# ETH_Wifi.net
KiCad netlist of a schematic drawn in Altium Designer
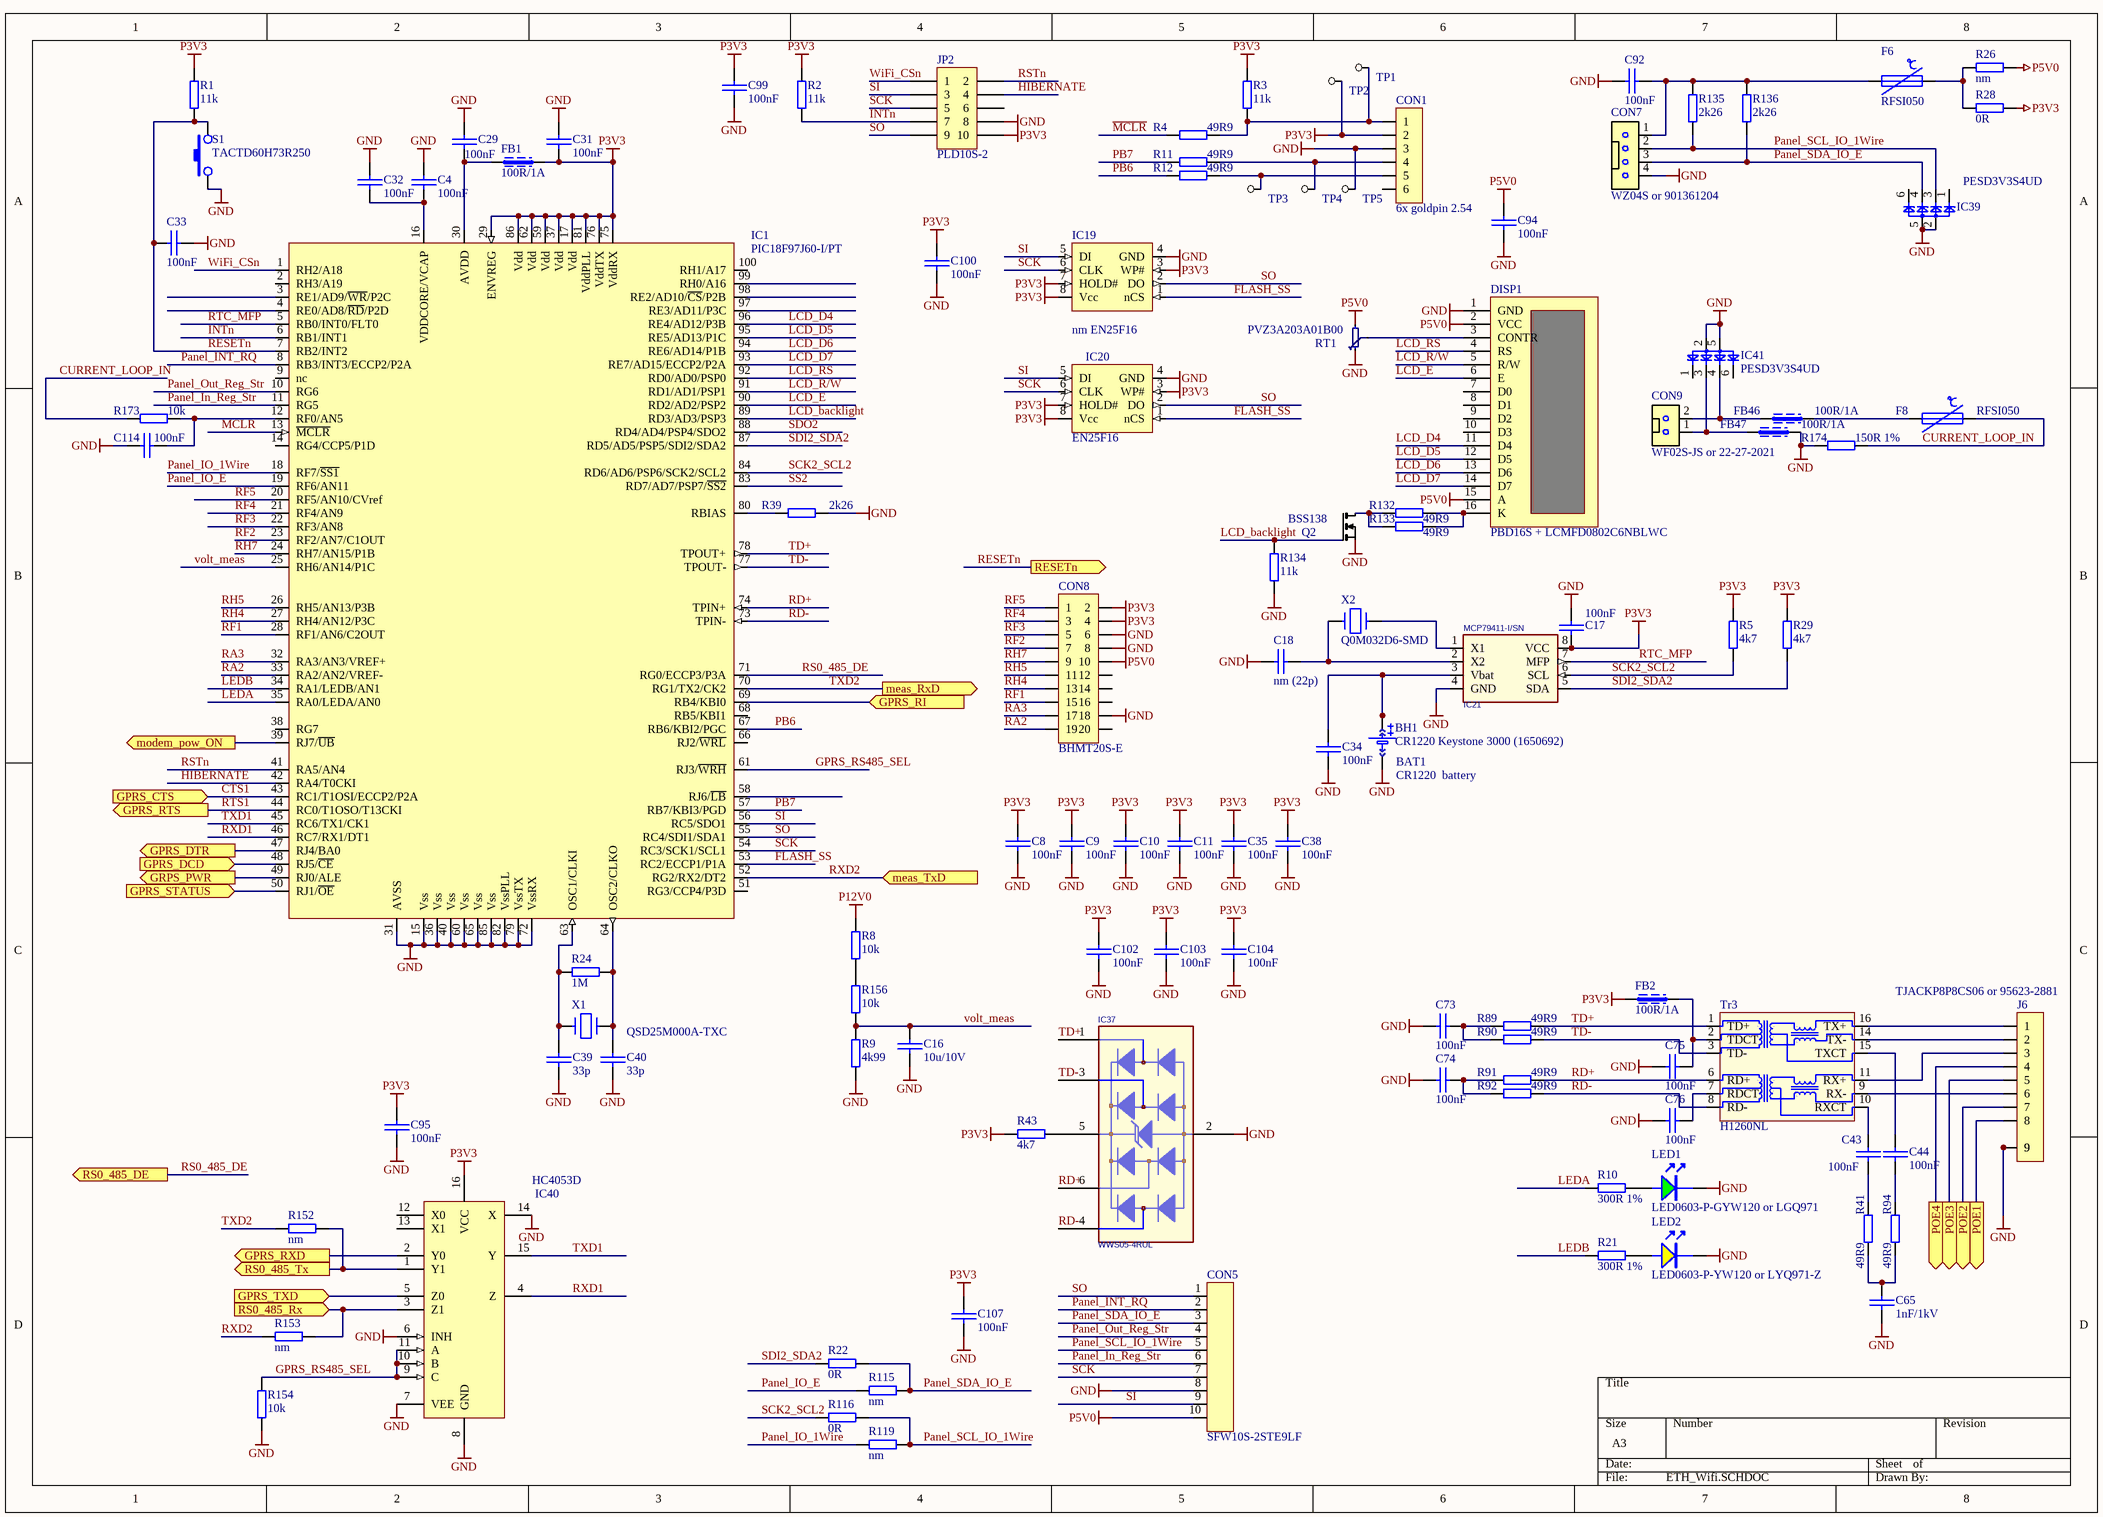
[diagram p0: ETH_Wifi.SCHDOC]

(export (version "E")
  (design (tool "Eeschema 10.0.6"))
  (components
    (comp (ref "BAT1")
      (value "CR1220  battery")
      (footprint "cr1220")
      (description "CR-21220 Battery 3V 35mAh")
      (libsource (lib "LIBRARY_SCH") (part "BATTERY_CR1220"))
    )
    (comp (ref "BH1")
      (value "CR1220 Keystone 3000 (1650692)")
      (footprint "CR1220_Keystone_3000")
      (description "CR-1220 Battery holder")
      (libsource (lib "LIBRARY_SCH") (part "BATTERY_HOLD_CR1220"))
    )
    (comp (ref "C4")
      (value "100nF")
      (footprint "0402C")
      (description "Capacitor SMD")
      (libsource (lib "LIBRARY_SCH") (part "CAP_SMD_0402"))
    )
    (comp (ref "C8")
      (value "100nF")
      (footprint "0402C")
      (description "Capacitor SMD")
      (libsource (lib "LIBRARY_SCH") (part "CAP_SMD_0402"))
    )
    (comp (ref "C9")
      (value "100nF")
      (footprint "0402C")
      (description "Capacitor SMD")
      (libsource (lib "LIBRARY_SCH") (part "CAP_SMD_0402"))
    )
    (comp (ref "C10")
      (value "100nF")
      (footprint "0402C")
      (description "Capacitor SMD")
      (libsource (lib "LIBRARY_SCH") (part "CAP_SMD_0402"))
    )
    (comp (ref "C11")
      (value "100nF")
      (footprint "0402C")
      (description "Capacitor SMD")
      (libsource (lib "LIBRARY_SCH") (part "CAP_SMD_0402"))
    )
    (comp (ref "C16")
      (value "10u/10V")
      (footprint "0805C")
      (description "Capacitor SMD")
      (libsource (lib "LIBRARY_SCH") (part "CAP_SMD_0805"))
    )
    (comp (ref "C17")
      (value "100nF")
      (footprint "0402C")
      (description "Capacitor SMD")
      (libsource (lib "LIBRARY_SCH") (part "CAP_SMD_0402"))
    )
    (comp (ref "C18")
      (value "nm (22p)")
      (footprint "0603C")
      (description "Capacitor SMD")
      (libsource (lib "LIBRARY_SCH") (part "CAP_SMD_0603"))
    )
    (comp (ref "C29")
      (value "100nF")
      (footprint "0402C")
      (description "Capacitor SMD")
      (libsource (lib "LIBRARY_SCH") (part "CAP_SMD_0402"))
    )
    (comp (ref "C31")
      (value "100nF")
      (footprint "0402C")
      (description "Capacitor SMD")
      (libsource (lib "LIBRARY_SCH") (part "CAP_SMD_0402"))
    )
    (comp (ref "C32")
      (value "100nF")
      (footprint "0402C")
      (description "Capacitor SMD")
      (libsource (lib "LIBRARY_SCH") (part "CAP_SMD_0402"))
    )
    (comp (ref "C33")
      (value "100nF")
      (footprint "0402C")
      (description "Capacitor SMD")
      (libsource (lib "LIBRARY_SCH") (part "CAP_SMD_0402"))
    )
    (comp (ref "C34")
      (value "100nF")
      (footprint "0402C")
      (description "Capacitor SMD")
      (libsource (lib "LIBRARY_SCH") (part "CAP_SMD_0402"))
    )
    (comp (ref "C35")
      (value "100nF")
      (footprint "0402C")
      (description "Capacitor SMD")
      (libsource (lib "LIBRARY_SCH") (part "CAP_SMD_0402"))
    )
    (comp (ref "C38")
      (value "100nF")
      (footprint "0402C")
      (description "Capacitor SMD")
      (libsource (lib "LIBRARY_SCH") (part "CAP_SMD_0402"))
    )
    (comp (ref "C39")
      (value "33p")
      (footprint "0603C")
      (description "Capacitor SMD")
      (libsource (lib "LIBRARY_SCH") (part "CAP_SMD"))
    )
    (comp (ref "C40")
      (value "33p")
      (footprint "0603C")
      (description "Capacitor SMD")
      (libsource (lib "LIBRARY_SCH") (part "CAP_SMD"))
    )
    (comp (ref "C43")
      (value "100nF")
      (footprint "0402C")
      (description "Capacitor SMD")
      (libsource (lib "LIBRARY_SCH") (part "CAP_SMD_0402"))
    )
    (comp (ref "C44")
      (value "100nF")
      (footprint "0402C")
      (description "Capacitor SMD")
      (libsource (lib "LIBRARY_SCH") (part "CAP_SMD_0402"))
    )
    (comp (ref "C65")
      (value "1nF/1kV")
      (footprint "1206C")
      (description "Capacitor SMD")
      (libsource (lib "LIBRARY_SCH") (part "CAP_SMD_1206"))
    )
    (comp (ref "C73")
      (value "100nF")
      (footprint "0402C")
      (description "Capacitor SMD")
      (libsource (lib "LIBRARY_SCH") (part "CAP_SMD_0402"))
    )
    (comp (ref "C74")
      (value "100nF")
      (footprint "0402C")
      (description "Capacitor SMD")
      (libsource (lib "LIBRARY_SCH") (part "CAP_SMD_0402"))
    )
    (comp (ref "C75")
      (value "100nF")
      (footprint "0402C")
      (description "Capacitor SMD")
      (libsource (lib "LIBRARY_SCH") (part "CAP_SMD_0402"))
    )
    (comp (ref "C76")
      (value "100nF")
      (footprint "0402C")
      (description "Capacitor SMD")
      (libsource (lib "LIBRARY_SCH") (part "CAP_SMD_0402"))
    )
    (comp (ref "C92")
      (value "100nF")
      (footprint "0402C")
      (description "Capacitor SMD")
      (libsource (lib "LIBRARY_SCH") (part "CAP_SMD_0402"))
    )
    (comp (ref "C94")
      (value "100nF")
      (footprint "0402C")
      (description "Capacitor SMD")
      (libsource (lib "LIBRARY_SCH") (part "CAP_SMD_0402"))
    )
    (comp (ref "C95")
      (value "100nF")
      (footprint "0402C")
      (description "Capacitor SMD")
      (libsource (lib "LIBRARY_SCH") (part "CAP_SMD_0402"))
    )
    (comp (ref "C99")
      (value "100nF")
      (footprint "0402C")
      (description "Capacitor SMD")
      (libsource (lib "LIBRARY_SCH") (part "CAP_SMD_0402"))
    )
    (comp (ref "C100")
      (value "100nF")
      (footprint "0402C")
      (description "Capacitor SMD")
      (libsource (lib "LIBRARY_SCH") (part "CAP_SMD_0402"))
    )
    (comp (ref "C102")
      (value "100nF")
      (footprint "0402C")
      (description "Capacitor SMD")
      (libsource (lib "LIBRARY_SCH") (part "CAP_SMD_0402"))
    )
    (comp (ref "C103")
      (value "100nF")
      (footprint "0402C")
      (description "Capacitor SMD")
      (libsource (lib "LIBRARY_SCH") (part "CAP_SMD_0402"))
    )
    (comp (ref "C104")
      (value "100nF")
      (footprint "0402C")
      (description "Capacitor SMD")
      (libsource (lib "LIBRARY_SCH") (part "CAP_SMD_0402"))
    )
    (comp (ref "C107")
      (value "100nF")
      (footprint "0402C")
      (description "Capacitor SMD")
      (libsource (lib "LIBRARY_SCH") (part "CAP_SMD_0402"))
    )
    (comp (ref "C114")
      (value "100nF")
      (footprint "0402C")
      (description "Capacitor SMD")
      (libsource (lib "LIBRARY_SCH") (part "CAP_SMD_0402"))
    )
    (comp (ref "CON1") (value "6x goldpin 2.54") (footprint "SIP6") (libsource (lib "*") (part "CON6")))
    (comp (ref "CON5")
      (value "SFW10S-2STE9LF")
      (footprint "SFW10S-2STE9LF")
      (description "FCI ZIF 1mm connector (Farnell)")
      (libsource (lib "ProjectLib") (part "CON_ZIF_10_1mm_SMT_V"))
    )
    (comp (ref "CON7")
      (value "WZ04S or 901361204")
      (footprint "WZ04S")
      (description "2.54mm crimped terminal header")
      (libsource (lib "ProjectLib") (part "CON_4_2.54_key"))
    )
    (comp (ref "CON8")
      (value "BHMT20S-E")
      (footprint "BHMT20S")
      (description "20 pin, IDC receptacle, 2mm")
      (libsource (lib "LIBRARY_SCH") (part "CON_IDC20_SMT_2mm"))
    )
    (comp (ref "CON9")
      (value "WF02S-JS or 22-27-2021")
      (footprint "CON_WF02S-LF")
      (description "2.54mm crimped terminal header")
      (libsource (lib "LIBRARY_SCH") (part "CON_2_2.54_key"))
    )
    (comp (ref "DISP1")
      (value "PBD16S + LCMFD0802C6NBLWC")
      (footprint "LCMFD0802C6NBLWC")
      (description "LCD character display socket with backlight")
      (libsource (lib "LIBRARY_SCH") (part "LCD_HD44780_LED_2x8"))
    )
    (comp (ref "F6")
      (value "RFSI050")
      (footprint "0805R")
      (description "50mA polymer FUSE")
      (libsource (lib "LIBRARY_SCH") (part "F_PTC_0.05A"))
    )
    (comp (ref "F8")
      (value "RFSI050")
      (footprint "0805R")
      (description "50mA polymer FUSE")
      (libsource (lib "LIBRARY_SCH") (part "F_PTC_0.05A"))
    )
    (comp (ref "FB1")
      (value "100R/1A")
      (footprint "0603L")
      (description "ferrite bead")
      (libsource (lib "*") (part "L_FERRITE_BEAD"))
    )
    (comp (ref "FB2")
      (value "100R/1A")
      (footprint "0603L")
      (description "ferrite bead")
      (libsource (lib "*") (part "L_FERRITE_BEAD"))
    )
    (comp (ref "FB46")
      (value "100R/1A")
      (footprint "0603L")
      (description "ferrite bead")
      (libsource (lib "LIBRARY_SCH") (part "L_FERRITE_BEAD"))
    )
    (comp (ref "FB47")
      (value "100R/1A")
      (footprint "0603L")
      (description "ferrite bead")
      (libsource (lib "LIBRARY_SCH") (part "L_FERRITE_BEAD"))
    )
    (comp (ref "IC1")
      (value "PIC18F97J60-I/PT")
      (footprint "lqfp100_12x12mm")
      (libsource (lib "ProjectLib") (part "UPC_PIC18F96J65_PT"))
    )
    (comp (ref "IC19")
      (value "nm EN25F16")
      (footprint "SO-8L")
      (description "FLASH (maritex)")
      (libsource (lib "LIBRARY_SCH") (part "MEM_EN25F16"))
    )
    (comp (ref "IC20")
      (value "EN25F16")
      (footprint "SO-8")
      (description "FLASH (maritex)")
      (libsource (lib "LIBRARY_SCH") (part "MEM_EN25F16"))
    )
    (comp (ref "IC21")
      (value "MCP79411-I/SN")
      (footprint "SO-8")
      (description "RTC with 1k EEPROM, RAM and 48bit unique ID")
      (libsource (lib "LIBRARY_SCH") (part "RTC_MCP79411"))
    )
    (comp (ref "IC37")
      (value "WWS05-4RUL")
      (description "TVS, 5V")
      (libsource (lib "LIBRARY_SCH") (part "D_TVS_WWS05-4RUL"))
    )
    (comp (ref "IC39")
      (value "PESD3V3S4UD")
      (footprint "SOT457")
      (description "3.3V TVS")
      (libsource (lib "LIBRARY_SCH") (part "D_TVS_PESD3V3S4UD"))
    )
    (comp (ref "IC40") (value "HC4053D") (footprint "SO-16") (libsource (lib "LIBRARY_SCH") (part "4053")))
    (comp (ref "IC41")
      (value "PESD3V3S4UD")
      (footprint "SOT457")
      (description "3.3V TVS")
      (libsource (lib "LIBRARY_SCH") (part "D_TVS_PESD3V3S4UD"))
    )
    (comp (ref "J6")
      (value "TJACKP8P8CS06 or 95623-2881")
      (footprint "ETH_VERT_95623-2881")
      (description "Modular 8pin (Maritex or Molex)")
      (libsource (lib "LIBRARY_SCH") (part "CON_MOD_8pin_V"))
    )
    (comp (ref "JP2")
      (value "PLD10S-2")
      (footprint "HEADER5X2")
      (description "Goldpin 2.54mm")
      (libsource (lib "LIBRARY_SCH") (part "CON_HEADER 5X2"))
    )
    (comp (ref "LED1")
      (value "LED0603-P-GYW120 or LGQ971")
      (footprint "led_0603G")
      (description "LED 0603 green")
      (libsource (lib "LIBRARY_SCH") (part "LED_0603G"))
    )
    (comp (ref "LED2")
      (value "LED0603-P-YW120 or LYQ971-Z")
      (footprint "led_0603B")
      (description "LED 0603 yellow")
      (libsource (lib "LIBRARY_SCH") (part "LED_0603Y"))
    )
    (comp (ref "Q2") (value "BSS138") (footprint "SOT-23") (libsource (lib "LIBRARY_SCH") (part "Q_BSS138")))
    (comp (ref "R1")
      (value "11k")
      (footprint "0603R")
      (description "SMD Resistor")
      (libsource (lib "*") (part "RES_SMD"))
    )
    (comp (ref "R2")
      (value "11k")
      (footprint "0603R")
      (description "SMD Resistor")
      (libsource (lib "*") (part "RES_SMD"))
    )
    (comp (ref "R3")
      (value "11k")
      (footprint "0603R")
      (description "SMD Resistor")
      (libsource (lib "*") (part "RES_SMD"))
    )
    (comp (ref "R4")
      (value "49R9")
      (footprint "0603R")
      (description "SMD Resistor")
      (libsource (lib "*") (part "RES_SMD"))
    )
    (comp (ref "R5")
      (value "4k7")
      (footprint "0402R")
      (description "SMD Resistor")
      (libsource (lib "LIBRARY_SCH") (part "RES_0402"))
    )
    (comp (ref "R8")
      (value "10k")
      (footprint "0402R")
      (description "SMD Resistor")
      (libsource (lib "LIBRARY_SCH") (part "RES_0402"))
    )
    (comp (ref "R9")
      (value "4k99")
      (footprint "0603R")
      (description "SMD Resistor")
      (libsource (lib "LIBRARY_SCH") (part "RES_0603"))
    )
    (comp (ref "R10")
      (value "300R 1%")
      (footprint "0603R")
      (description "SMD Resistor")
      (libsource (lib "LIBRARY_SCH") (part "RES_SMD"))
    )
    (comp (ref "R11")
      (value "49R9")
      (footprint "0603R")
      (description "SMD Resistor")
      (libsource (lib "*") (part "RES_SMD"))
    )
    (comp (ref "R12")
      (value "49R9")
      (footprint "0603R")
      (description "SMD Resistor")
      (libsource (lib "*") (part "RES_SMD"))
    )
    (comp (ref "R21")
      (value "300R 1%")
      (footprint "0603R")
      (description "SMD Resistor")
      (libsource (lib "LIBRARY_SCH") (part "RES_SMD"))
    )
    (comp (ref "R22")
      (value "0R")
      (footprint "0603R")
      (description "SMD Resistor")
      (libsource (lib "LIBRARY_SCH") (part "RES_0603"))
    )
    (comp (ref "R24")
      (value "1M")
      (footprint "0603R")
      (description "SMD Resistor")
      (libsource (lib "*") (part "RES_SMD"))
    )
    (comp (ref "R26")
      (value "nm")
      (footprint "0603R")
      (description "SMD Resistor")
      (libsource (lib "") (part "RES_0603_1"))
    )
    (comp (ref "R28")
      (value "0R")
      (footprint "0603R")
      (description "SMD Resistor")
      (libsource (lib "") (part "RES_0603_1"))
    )
    (comp (ref "R29")
      (value "4k7")
      (footprint "0402R")
      (description "SMD Resistor")
      (libsource (lib "LIBRARY_SCH") (part "RES_0402"))
    )
    (comp (ref "R39")
      (value "2k26")
      (footprint "0603R")
      (description "SMD Resistor")
      (libsource (lib "LIBRARY_SCH") (part "RES_SMD"))
    )
    (comp (ref "R41")
      (value "49R9")
      (footprint "0603")
      (description "SMD Resistor")
      (libsource (lib "*") (part "RES_SMD"))
    )
    (comp (ref "R43")
      (value "4k7")
      (footprint "0402R")
      (description "SMD Resistor")
      (libsource (lib "LIBRARY_SCH") (part "RES_0402"))
    )
    (comp (ref "R89")
      (value "49R9")
      (footprint "0603R")
      (description "SMD Resistor")
      (libsource (lib "LIBRARY_SCH") (part "RES_SMD"))
    )
    (comp (ref "R90")
      (value "49R9")
      (footprint "0603R")
      (description "SMD Resistor")
      (libsource (lib "*") (part "RES_SMD"))
    )
    (comp (ref "R91")
      (value "49R9")
      (footprint "0603R")
      (description "SMD Resistor")
      (libsource (lib "*") (part "RES_SMD"))
    )
    (comp (ref "R92")
      (value "49R9")
      (footprint "0603R")
      (description "SMD Resistor")
      (libsource (lib "*") (part "RES_SMD"))
    )
    (comp (ref "R94")
      (value "49R9")
      (footprint "0603")
      (description "SMD Resistor")
      (libsource (lib "*") (part "RES_SMD"))
    )
    (comp (ref "R115")
      (value "nm")
      (footprint "0603R")
      (description "SMD Resistor")
      (libsource (lib "LIBRARY_SCH") (part "RES_0603"))
    )
    (comp (ref "R116")
      (value "0R")
      (footprint "0603R")
      (description "SMD Resistor")
      (libsource (lib "LIBRARY_SCH") (part "RES_0603"))
    )
    (comp (ref "R119")
      (value "nm")
      (footprint "0603R")
      (description "SMD Resistor")
      (libsource (lib "LIBRARY_SCH") (part "RES_0603"))
    )
    (comp (ref "R132")
      (value "49R9")
      (footprint "0603R")
      (description "SMD Resistor")
      (libsource (lib "") (part "RES_0603_1"))
    )
    (comp (ref "R133")
      (value "49R9")
      (footprint "0603R")
      (description "SMD Resistor")
      (libsource (lib "") (part "RES_0603_1"))
    )
    (comp (ref "R134")
      (value "11k")
      (footprint "0603R")
      (description "SMD Resistor")
      (libsource (lib "*") (part "RES_SMD"))
    )
    (comp (ref "R135")
      (value "2k26")
      (footprint "0603R")
      (description "SMD Resistor")
      (libsource (lib "") (part "RES_0603_1"))
    )
    (comp (ref "R136")
      (value "2k26")
      (footprint "0603R")
      (description "SMD Resistor")
      (libsource (lib "") (part "RES_0603_1"))
    )
    (comp (ref "R152")
      (value "nm")
      (footprint "0603R")
      (description "SMD Resistor")
      (libsource (lib "LIBRARY_SCH") (part "RES_0603"))
    )
    (comp (ref "R153")
      (value "nm")
      (footprint "0603R")
      (description "SMD Resistor")
      (libsource (lib "LIBRARY_SCH") (part "RES_0603"))
    )
    (comp (ref "R154")
      (value "10k")
      (footprint "0402R")
      (description "SMD Resistor")
      (libsource (lib "LIBRARY_SCH") (part "RES_0402"))
    )
    (comp (ref "R156")
      (value "10k")
      (footprint "0402R")
      (description "SMD Resistor")
      (libsource (lib "LIBRARY_SCH") (part "RES_0402"))
    )
    (comp (ref "R173")
      (value "10k")
      (footprint "0402R")
      (description "SMD Resistor")
      (libsource (lib "LIBRARY_SCH") (part "RES_0402"))
    )
    (comp (ref "R174")
      (value "150R 1%")
      (footprint "0805R")
      (description "SMD Resistor")
      (libsource (lib "LIBRARY_SCH") (part "RES_0805"))
    )
    (comp (ref "RT1")
      (value "PVZ3A203A01B00")
      (footprint "TRIMPOT_PVZ3A")
      (description "carbon SMD trimpot (Farnell)")
      (libsource (lib "LIBRARY_SCH") (part "TRIMPOT_SMD_CARBON"))
    )
    (comp (ref "S1")
      (value "TACTD60H73R250")
      (footprint "TACT-DQ62H73G160")
      (description "Push button 7.3mm")
      (libsource (lib "LIBRARY_SCH") (part "SW-PB"))
    )
    (comp (ref "TP1")
      (value "TP_nMCLR")
      (footprint "TP_large")
      (description "Testpoint")
      (libsource (lib "LIBRARY_SCH") (part "TP"))
    )
    (comp (ref "TP2")
      (value "TP_3V3_ctrl")
      (footprint "TP_large")
      (description "Testpoint")
      (libsource (lib "LIBRARY_SCH") (part "TP"))
    )
    (comp (ref "TP3")
      (value "TP_PB6")
      (footprint "TP_large")
      (description "Testpoint")
      (libsource (lib "LIBRARY_SCH") (part "TP"))
    )
    (comp (ref "TP4")
      (value "TP_PB7")
      (footprint "TP_large")
      (description "Testpoint")
      (libsource (lib "LIBRARY_SCH") (part "TP"))
    )
    (comp (ref "TP5")
      (value "TP_GND_ctrl")
      (footprint "TP_large")
      (description "Testpoint")
      (libsource (lib "LIBRARY_SCH") (part "TP"))
    )
    (comp (ref "Tr3")
      (value "H1260NL")
      (footprint "H1260NL")
      (description "ethernet trafo (TME)")
      (libsource (lib "*") (part "TR_H1260NL"))
    )
    (comp (ref "X1")
      (value "QSD25M000A-TXC")
      (footprint "HC-49SM")
      (description "Crystal oscillator")
      (libsource (lib "LIBRARY_SCH") (part "CRYSTAL"))
    )
    (comp (ref "X2")
      (value "Q0M032D6-SMD")
      (footprint "crystal_85SMX")
      (description "Crystal oscillator 32k (Maritex)")
      (libsource (lib "LIBRARY_SCH") (part "X_CRYSTAL_32k_SMD"))
    )
  )
  (nets
    (net (code "1") (name "/CTS1") (class "Default")
      (node (ref "IC1") (pin "43") (pinfunction "RC1/T1OSI/ECCP2/P2A_43") (pintype "bidirectional"))
    )
    (net (code "2") (name "/CURRENT_LOOP_IN") (class "Default")
      (node (ref "F8") (pin "2") (pinfunction "2_2") (pintype "passive"))
      (node (ref "R173") (pin "1") (pinfunction "1_1") (pintype "passive"))
      (node (ref "R174") (pin "2") (pinfunction "2_2") (pintype "passive"))
    )
    (net (code "3") (name "/FLASH_SS") (class "Default")
      (node (ref "IC1") (pin "53") (pinfunction "RC2/ECCP1/P1A_53") (pintype "bidirectional"))
      (node (ref "IC19") (pin "1") (pinfunction "nCS_1") (pintype "input"))
      (node (ref "IC20") (pin "1") (pinfunction "nCS_1") (pintype "input"))
    )
    (net (code "4") (name "/GPRS_DCD") (class "Default")
      (node (ref "IC1") (pin "48") (pinfunction "RJ5/~{CE}_48") (pintype "bidirectional"))
    )
    (net (code "5") (name "/GPRS_DTR") (class "Default")
      (node (ref "IC1") (pin "47") (pinfunction "RJ4/BA0_47") (pintype "bidirectional"))
    )
    (net (code "6") (name "/GPRS_RI") (class "Default")
      (node (ref "IC1") (pin "69") (pinfunction "RB4/KBI0_69") (pintype "bidirectional"))
    )
    (net (code "7") (name "/GPRS_RS485_SEL") (class "Default")
      (node (ref "IC1") (pin "61") (pinfunction "RJ3/~{WRH}_61") (pintype "bidirectional"))
      (node (ref "IC40") (pin "10") (pinfunction "B_10") (pintype "input"))
      (node (ref "IC40") (pin "11") (pinfunction "A_11") (pintype "input"))
      (node (ref "IC40") (pin "9") (pinfunction "C_9") (pintype "input"))
      (node (ref "R154") (pin "2") (pinfunction "2_2") (pintype "passive"))
    )
    (net (code "8") (name "/GPRS_RXD") (class "Default")
      (node (ref "IC40") (pin "2") (pinfunction "Y0_2") (pintype "passive"))
    )
    (net (code "9") (name "/GPRS_STATUS") (class "Default")
      (node (ref "IC1") (pin "50") (pinfunction "RJ1/~{OE}_50") (pintype "bidirectional"))
    )
    (net (code "10") (name "/GPRS_TXD") (class "Default")
      (node (ref "IC40") (pin "5") (pinfunction "Z0_5") (pintype "passive"))
    )
    (net (code "11") (name "/GRPS_PWR") (class "Default")
      (node (ref "IC1") (pin "49") (pinfunction "RJ0/ALE_49") (pintype "bidirectional"))
    )
    (net (code "12") (name "/HIBERNATE") (class "Default")
      (node (ref "IC1") (pin "42") (pinfunction "RA4/T0CKI_42") (pintype "bidirectional"))
      (node (ref "JP2") (pin "4") (pinfunction "4_4") (pintype "passive"))
    )
    (net (code "13") (name "/INTn") (class "Default")
      (node (ref "IC1") (pin "6") (pinfunction "RB1/INT1_6") (pintype "bidirectional"))
      (node (ref "JP2") (pin "7") (pinfunction "7_7") (pintype "passive"))
      (node (ref "R2") (pin "1") (pinfunction "1_1") (pintype "passive"))
    )
    (net (code "14") (name "/LCD_D4") (class "Default")
      (node (ref "DISP1") (pin "11") (pinfunction "D4_11") (pintype "passive"))
      (node (ref "IC1") (pin "96") (pinfunction "RE4/AD12/P3B_96") (pintype "bidirectional"))
    )
    (net (code "15") (name "/LCD_D5") (class "Default")
      (node (ref "DISP1") (pin "12") (pinfunction "D5_12") (pintype "passive"))
      (node (ref "IC1") (pin "95") (pinfunction "RE5/AD13/P1C_95") (pintype "bidirectional"))
    )
    (net (code "16") (name "/LCD_D6") (class "Default")
      (node (ref "DISP1") (pin "13") (pinfunction "D6_13") (pintype "passive"))
      (node (ref "IC1") (pin "94") (pinfunction "RE6/AD14/P1B_94") (pintype "bidirectional"))
    )
    (net (code "17") (name "/LCD_D7") (class "Default")
      (node (ref "DISP1") (pin "14") (pinfunction "D7_14") (pintype "passive"))
      (node (ref "IC1") (pin "93") (pinfunction "RE7/AD15/ECCP2/P2A_93") (pintype "bidirectional"))
    )
    (net (code "18") (name "/LCD_E") (class "Default")
      (node (ref "DISP1") (pin "6") (pinfunction "E_6") (pintype "passive"))
      (node (ref "IC1") (pin "90") (pinfunction "RD2/AD2/PSP2_90") (pintype "bidirectional"))
    )
    (net (code "19") (name "/LCD_RS") (class "Default")
      (node (ref "DISP1") (pin "4") (pinfunction "RS_4") (pintype "passive"))
      (node (ref "IC1") (pin "92") (pinfunction "RD0/AD0/PSP0_92") (pintype "bidirectional"))
    )
    (net (code "20") (name "/LCD_R{slash}W") (class "Default")
      (node (ref "DISP1") (pin "5") (pinfunction "R/W_5") (pintype "passive"))
      (node (ref "IC1") (pin "91") (pinfunction "RD1/AD1/PSP1_91") (pintype "bidirectional"))
    )
    (net (code "21") (name "/LCD_backlight") (class "Default")
      (node (ref "IC1") (pin "89") (pinfunction "RD3/AD3/PSP3_89") (pintype "bidirectional"))
      (node (ref "Q2") (pin "1") (pinfunction "G_1") (pintype "input"))
      (node (ref "R134") (pin "2") (pinfunction "2_2") (pintype "passive"))
    )
    (net (code "22") (name "/LEDA") (class "Default")
      (node (ref "IC1") (pin "35") (pinfunction "RA0/LEDA/AN0_35") (pintype "bidirectional"))
      (node (ref "R10") (pin "2") (pinfunction "2_2") (pintype "passive"))
    )
    (net (code "23") (name "/LEDB") (class "Default")
      (node (ref "IC1") (pin "34") (pinfunction "RA1/LEDB/AN1_34") (pintype "bidirectional"))
      (node (ref "R21") (pin "2") (pinfunction "2_2") (pintype "passive"))
    )
    (net (code "24") (name "/PB6") (class "Default")
      (node (ref "IC1") (pin "67") (pinfunction "RB6/KBI2/PGC_67") (pintype "bidirectional"))
      (node (ref "R12") (pin "1") (pinfunction "1_1") (pintype "passive"))
    )
    (net (code "25") (name "/PB7") (class "Default")
      (node (ref "IC1") (pin "57") (pinfunction "RB7/KBI3/PGD_57") (pintype "bidirectional"))
      (node (ref "R11") (pin "1") (pinfunction "1_1") (pintype "passive"))
    )
    (net (code "26") (name "/POE1") (class "Default")
      (node (ref "J6") (pin "8") (pinfunction "8_8") (pintype "passive"))
    )
    (net (code "27") (name "/POE2") (class "Default")
      (node (ref "J6") (pin "7") (pinfunction "7_7") (pintype "passive"))
    )
    (net (code "28") (name "/POE3") (class "Default")
      (node (ref "J6") (pin "5") (pinfunction "5_5") (pintype "passive"))
    )
    (net (code "29") (name "/POE4") (class "Default")
      (node (ref "J6") (pin "4") (pinfunction "4_4") (pintype "passive"))
    )
    (net (code "30") (name "/Panel_INT_RQ") (class "Default")
      (node (ref "CON5") (pin "2") (pinfunction "2_2") (pintype "passive"))
      (node (ref "IC1") (pin "8") (pinfunction "RB3/INT3/ECCP2/P2A_8") (pintype "bidirectional"))
    )
    (net (code "31") (name "/Panel_IO_1Wire") (class "Default")
      (node (ref "IC1") (pin "18") (pinfunction "RF7/~{SS1}_18") (pintype "bidirectional"))
      (node (ref "R119") (pin "2") (pinfunction "2_2") (pintype "passive"))
    )
    (net (code "32") (name "/Panel_IO_E") (class "Default")
      (node (ref "IC1") (pin "19") (pinfunction "RF6/AN11_19") (pintype "bidirectional"))
      (node (ref "R115") (pin "2") (pinfunction "2_2") (pintype "passive"))
    )
    (net (code "33") (name "/Panel_In_Reg_Str") (class "Default")
      (node (ref "CON5") (pin "6") (pinfunction "6_6") (pintype "passive"))
      (node (ref "IC1") (pin "11") (pinfunction "RG5_11") (pintype "bidirectional"))
    )
    (net (code "34") (name "/Panel_Out_Reg_Str") (class "Default")
      (node (ref "CON5") (pin "4") (pinfunction "4_4") (pintype "passive"))
      (node (ref "IC1") (pin "10") (pinfunction "RG6_10") (pintype "bidirectional"))
    )
    (net (code "35") (name "/Panel_SCL_IO_1Wire") (class "Default")
      (node (ref "CON5") (pin "5") (pinfunction "5_5") (pintype "passive"))
      (node (ref "CON7") (pin "2") (pinfunction "2_2") (pintype "bidirectional"))
      (node (ref "IC39") (pin "3") (pinfunction "3_3") (pintype "passive"))
      (node (ref "R116") (pin "1") (pinfunction "1_1") (pintype "passive"))
      (node (ref "R119") (pin "1") (pinfunction "1_1") (pintype "passive"))
      (node (ref "R135") (pin "2") (pinfunction "2_2") (pintype "passive"))
    )
    (net (code "36") (name "/Panel_SDA_IO_E") (class "Default")
      (node (ref "CON5") (pin "3") (pinfunction "3_3") (pintype "passive"))
      (node (ref "CON7") (pin "3") (pinfunction "3_3") (pintype "bidirectional"))
      (node (ref "IC39") (pin "4") (pinfunction "4_4") (pintype "passive"))
      (node (ref "R115") (pin "1") (pinfunction "1_1") (pintype "passive"))
      (node (ref "R136") (pin "2") (pinfunction "2_2") (pintype "passive"))
      (node (ref "R22") (pin "1") (pinfunction "1_1") (pintype "passive"))
    )
    (net (code "37") (name "/RA2") (class "Default")
      (node (ref "CON8") (pin "19") (pinfunction "19_19") (pintype "passive"))
      (node (ref "IC1") (pin "33") (pinfunction "RA2/AN2/VREF-_33") (pintype "bidirectional"))
    )
    (net (code "38") (name "/RA3") (class "Default")
      (node (ref "CON8") (pin "17") (pinfunction "17_17") (pintype "passive"))
      (node (ref "IC1") (pin "32") (pinfunction "RA3/AN3/VREF+_32") (pintype "bidirectional"))
    )
    (net (code "39") (name "/RD+") (class "Default")
      (node (ref "IC1") (pin "74") (pinfunction "TPIN+_74") (pintype "input"))
      (node (ref "IC37") (pin "6") (pinfunction "6_6") (pintype "passive"))
      (node (ref "R91") (pin "2") (pinfunction "2_2") (pintype "passive"))
      (node (ref "Tr3") (pin "6") (pinfunction "RD+_6") (pintype "passive"))
    )
    (net (code "40") (name "/RD-") (class "Default")
      (node (ref "IC1") (pin "73") (pinfunction "TPIN-_73") (pintype "input"))
      (node (ref "IC37") (pin "4") (pinfunction "4_4") (pintype "passive"))
      (node (ref "R92") (pin "2") (pinfunction "2_2") (pintype "passive"))
      (node (ref "Tr3") (pin "8") (pinfunction "RD-_8") (pintype "passive"))
    )
    (net (code "41") (name "/RESETn") (class "Default")
      (node (ref "C33") (pin "1") (pinfunction "1_1") (pintype "passive"))
      (node (ref "IC1") (pin "7") (pinfunction "RB2/INT2_7") (pintype "bidirectional"))
      (node (ref "R1") (pin "1") (pinfunction "1_1") (pintype "passive"))
      (node (ref "S1") (pin "2") (pinfunction "2_2") (pintype "passive"))
    )
    (net (code "42") (name "/RF1") (class "Default")
      (node (ref "CON8") (pin "15") (pinfunction "15_15") (pintype "passive"))
      (node (ref "IC1") (pin "28") (pinfunction "RF1/AN6/C2OUT_28") (pintype "bidirectional"))
    )
    (net (code "43") (name "/RF2") (class "Default")
      (node (ref "CON8") (pin "7") (pinfunction "7_7") (pintype "passive"))
      (node (ref "IC1") (pin "23") (pinfunction "RF2/AN7/C1OUT_23") (pintype "bidirectional"))
    )
    (net (code "44") (name "/RF3") (class "Default")
      (node (ref "CON8") (pin "5") (pinfunction "5_5") (pintype "passive"))
      (node (ref "IC1") (pin "22") (pinfunction "RF3/AN8_22") (pintype "bidirectional"))
    )
    (net (code "45") (name "/RF4") (class "Default")
      (node (ref "CON8") (pin "3") (pinfunction "3_3") (pintype "passive"))
      (node (ref "IC1") (pin "21") (pinfunction "RF4/AN9_21") (pintype "bidirectional"))
    )
    (net (code "46") (name "/RF5") (class "Default")
      (node (ref "CON8") (pin "1") (pinfunction "1_1") (pintype "passive"))
      (node (ref "IC1") (pin "20") (pinfunction "RF5/AN10/CVref_20") (pintype "bidirectional"))
    )
    (net (code "47") (name "/RH4") (class "Default")
      (node (ref "CON8") (pin "13") (pinfunction "13_13") (pintype "passive"))
      (node (ref "IC1") (pin "27") (pinfunction "RH4/AN12/P3C_27") (pintype "bidirectional"))
    )
    (net (code "48") (name "/RH5") (class "Default")
      (node (ref "CON8") (pin "11") (pinfunction "11_11") (pintype "passive"))
      (node (ref "IC1") (pin "26") (pinfunction "RH5/AN13/P3B_26") (pintype "bidirectional"))
    )
    (net (code "49") (name "/RH7") (class "Default")
      (node (ref "CON8") (pin "9") (pinfunction "9_9") (pintype "passive"))
      (node (ref "IC1") (pin "24") (pinfunction "RH7/AN15/P1B_24") (pintype "bidirectional"))
    )
    (net (code "50") (name "/RS0_485_DE") (class "Default")
      (node (ref "IC1") (pin "71") (pinfunction "RG0/ECCP3/P3A_71") (pintype "bidirectional"))
    )
    (net (code "51") (name "/RS0_485_Rx") (class "Default")
      (node (ref "IC40") (pin "3") (pinfunction "Z1_3") (pintype "passive"))
      (node (ref "R153") (pin "1") (pinfunction "1_1") (pintype "passive"))
    )
    (net (code "52") (name "/RS0_485_Tx") (class "Default")
      (node (ref "IC40") (pin "1") (pinfunction "Y1_1") (pintype "passive"))
      (node (ref "R152") (pin "1") (pinfunction "1_1") (pintype "passive"))
    )
    (net (code "53") (name "/RSTn") (class "Default")
      (node (ref "IC1") (pin "41") (pinfunction "RA5/AN4_41") (pintype "bidirectional"))
      (node (ref "JP2") (pin "2") (pinfunction "2_2") (pintype "passive"))
    )
    (net (code "54") (name "/RTC_MFP") (class "Default")
      (node (ref "IC1") (pin "5") (pinfunction "RB0/INT0/FLT0_5") (pintype "bidirectional"))
      (node (ref "IC21") (pin "7") (pinfunction "MFP_7") (pintype "output"))
    )
    (net (code "55") (name "/RTS1") (class "Default")
      (node (ref "IC1") (pin "44") (pinfunction "RC0/T1OSO/T13CKI_44") (pintype "bidirectional"))
    )
    (net (code "56") (name "/RXD1") (class "Default")
      (node (ref "IC1") (pin "46") (pinfunction "RC7/RX1/DT1_46") (pintype "bidirectional"))
      (node (ref "IC40") (pin "4") (pinfunction "Z_4") (pintype "passive"))
    )
    (net (code "57") (name "/RXD2") (class "Default")
      (node (ref "IC1") (pin "52") (pinfunction "RG2/RX2/DT2_52") (pintype "bidirectional"))
      (node (ref "R153") (pin "2") (pinfunction "2_2") (pintype "passive"))
    )
    (net (code "58") (name "/SCK") (class "Default")
      (node (ref "CON5") (pin "7") (pinfunction "7_7") (pintype "passive"))
      (node (ref "IC1") (pin "54") (pinfunction "RC3/SCK1/SCL1_54") (pintype "bidirectional"))
      (node (ref "IC19") (pin "6") (pinfunction "CLK_6") (pintype "input"))
      (node (ref "IC20") (pin "6") (pinfunction "CLK_6") (pintype "input"))
      (node (ref "JP2") (pin "5") (pinfunction "5_5") (pintype "passive"))
    )
    (net (code "59") (name "/SCK2_SCL2") (class "Default")
      (node (ref "IC1") (pin "84") (pinfunction "RD6/AD6/PSP6/SCK2/SCL2_84") (pintype "bidirectional"))
      (node (ref "IC21") (pin "6") (pinfunction "SCL_6") (pintype "input"))
      (node (ref "R116") (pin "2") (pinfunction "2_2") (pintype "passive"))
      (node (ref "R5") (pin "2") (pinfunction "2_2") (pintype "passive"))
    )
    (net (code "60") (name "/SDI2_SDA2") (class "Default")
      (node (ref "IC1") (pin "87") (pinfunction "RD5/AD5/PSP5/SDI2/SDA2_87") (pintype "bidirectional"))
      (node (ref "IC21") (pin "5") (pinfunction "SDA_5") (pintype "bidirectional"))
      (node (ref "R22") (pin "2") (pinfunction "2_2") (pintype "passive"))
      (node (ref "R29") (pin "2") (pinfunction "2_2") (pintype "passive"))
    )
    (net (code "61") (name "/SDO2") (class "Default")
      (node (ref "IC1") (pin "88") (pinfunction "RD4/AD4/PSP4/SDO2_88") (pintype "bidirectional"))
    )
    (net (code "62") (name "/SI") (class "Default")
      (node (ref "CON5") (pin "9") (pinfunction "9_9") (pintype "passive"))
      (node (ref "IC1") (pin "56") (pinfunction "RC5/SDO1_56") (pintype "bidirectional"))
      (node (ref "IC19") (pin "5") (pinfunction "DI_5") (pintype "input"))
      (node (ref "IC20") (pin "5") (pinfunction "DI_5") (pintype "input"))
      (node (ref "JP2") (pin "3") (pinfunction "3_3") (pintype "passive"))
    )
    (net (code "63") (name "/SO") (class "Default")
      (node (ref "CON5") (pin "1") (pinfunction "1_1") (pintype "passive"))
      (node (ref "IC1") (pin "55") (pinfunction "RC4/SDI1/SDA1_55") (pintype "bidirectional"))
      (node (ref "IC19") (pin "2") (pinfunction "DO_2") (pintype "output"))
      (node (ref "IC20") (pin "2") (pinfunction "DO_2") (pintype "output"))
      (node (ref "JP2") (pin "9") (pinfunction "9_9") (pintype "passive"))
    )
    (net (code "64") (name "/SS2") (class "Default")
      (node (ref "IC1") (pin "83") (pinfunction "RD7/AD7/PSP7/~{SS2}_83") (pintype "bidirectional"))
    )
    (net (code "65") (name "/TD+") (class "Default")
      (node (ref "IC1") (pin "78") (pinfunction "TPOUT+_78") (pintype "output"))
      (node (ref "IC37") (pin "1") (pinfunction "1_1") (pintype "passive"))
      (node (ref "R89") (pin "2") (pinfunction "2_2") (pintype "passive"))
      (node (ref "Tr3") (pin "1") (pinfunction "TD+_1") (pintype "passive"))
    )
    (net (code "66") (name "/TD-") (class "Default")
      (node (ref "IC1") (pin "77") (pinfunction "TPOUT-_77") (pintype "output"))
      (node (ref "IC37") (pin "3") (pinfunction "3_3") (pintype "passive"))
      (node (ref "R90") (pin "2") (pinfunction "2_2") (pintype "passive"))
      (node (ref "Tr3") (pin "3") (pinfunction "TD-_3") (pintype "passive"))
    )
    (net (code "67") (name "/TXD1") (class "Default")
      (node (ref "IC1") (pin "45") (pinfunction "RC6/TX1/CK1_45") (pintype "bidirectional"))
      (node (ref "IC40") (pin "15") (pinfunction "Y_15") (pintype "passive"))
    )
    (net (code "68") (name "/TXD2") (class "Default")
      (node (ref "IC1") (pin "70") (pinfunction "RG1/TX2/CK2_70") (pintype "bidirectional"))
      (node (ref "R152") (pin "2") (pinfunction "2_2") (pintype "passive"))
    )
    (net (code "69") (name "/WiFi_CSn") (class "Default")
      (node (ref "IC1") (pin "1") (pinfunction "RH2/A18_1") (pintype "bidirectional"))
      (node (ref "JP2") (pin "1") (pinfunction "1_1") (pintype "passive"))
    )
    (net (code "70") (name "/modem_pow_ON") (class "Default")
      (node (ref "IC1") (pin "39") (pinfunction "RJ7/~{UB}_39") (pintype "bidirectional"))
    )
    (net (code "71") (name "/volt_meas") (class "Default")
      (node (ref "C16") (pin "1") (pinfunction "1_1") (pintype "passive"))
      (node (ref "IC1") (pin "25") (pinfunction "RH6/AN14/P1C_25") (pintype "bidirectional"))
      (node (ref "R156") (pin "1") (pinfunction "1_1") (pintype "passive"))
      (node (ref "R9") (pin "2") (pinfunction "2_2") (pintype "passive"))
    )
    (net (code "72") (name "/~{MCLR}") (class "Default")
      (node (ref "IC1") (pin "13") (pinfunction "~{MCLR}_13") (pintype "input"))
      (node (ref "R4") (pin "1") (pinfunction "1_1") (pintype "passive"))
    )
    (net (code "73") (name "GND") (class "Default")
      (node (ref "BH1") (pin "neg") (pinfunction "+_neg") (pintype "power_in"))
      (node (ref "C10") (pin "2") (pinfunction "2_2") (pintype "passive"))
      (node (ref "C100") (pin "2") (pinfunction "2_2") (pintype "passive"))
      (node (ref "C102") (pin "2") (pinfunction "2_2") (pintype "passive"))
      (node (ref "C103") (pin "2") (pinfunction "2_2") (pintype "passive"))
      (node (ref "C104") (pin "2") (pinfunction "2_2") (pintype "passive"))
      (node (ref "C107") (pin "2") (pinfunction "2_2") (pintype "passive"))
      (node (ref "C11") (pin "2") (pinfunction "2_2") (pintype "passive"))
      (node (ref "C114") (pin "1") (pinfunction "1_1") (pintype "passive"))
      (node (ref "C16") (pin "2") (pinfunction "2_2") (pintype "passive"))
      (node (ref "C17") (pin "2") (pinfunction "2_2") (pintype "passive"))
      (node (ref "C18") (pin "2") (pinfunction "2_2") (pintype "passive"))
      (node (ref "C29") (pin "1") (pinfunction "1_1") (pintype "passive"))
      (node (ref "C31") (pin "1") (pinfunction "1_1") (pintype "passive"))
      (node (ref "C32") (pin "1") (pinfunction "1_1") (pintype "passive"))
      (node (ref "C33") (pin "2") (pinfunction "2_2") (pintype "passive"))
      (node (ref "C34") (pin "2") (pinfunction "2_2") (pintype "passive"))
      (node (ref "C35") (pin "2") (pinfunction "2_2") (pintype "passive"))
      (node (ref "C38") (pin "2") (pinfunction "2_2") (pintype "passive"))
      (node (ref "C39") (pin "1") (pinfunction "1_1") (pintype "passive"))
      (node (ref "C4") (pin "1") (pinfunction "1_1") (pintype "passive"))
      (node (ref "C40") (pin "1") (pinfunction "1_1") (pintype "passive"))
      (node (ref "C65") (pin "2") (pinfunction "2_2") (pintype "passive"))
      (node (ref "C73") (pin "1") (pinfunction "1_1") (pintype "passive"))
      (node (ref "C74") (pin "1") (pinfunction "1_1") (pintype "passive"))
      (node (ref "C75") (pin "1") (pinfunction "1_1") (pintype "passive"))
      (node (ref "C76") (pin "1") (pinfunction "1_1") (pintype "passive"))
      (node (ref "C8") (pin "1") (pinfunction "1_1") (pintype "passive"))
      (node (ref "C9") (pin "2") (pinfunction "2_2") (pintype "passive"))
      (node (ref "C92") (pin "1") (pinfunction "1_1") (pintype "passive"))
      (node (ref "C94") (pin "1") (pinfunction "1_1") (pintype "passive"))
      (node (ref "C95") (pin "2") (pinfunction "2_2") (pintype "passive"))
      (node (ref "C99") (pin "2") (pinfunction "2_2") (pintype "passive"))
      (node (ref "CON1") (pin "3") (pinfunction "3_3") (pintype "passive"))
      (node (ref "CON5") (pin "8") (pinfunction "8_8") (pintype "passive"))
      (node (ref "CON7") (pin "4") (pinfunction "4_4") (pintype "bidirectional"))
      (node (ref "CON8") (pin "18") (pinfunction "18_18") (pintype "passive"))
      (node (ref "CON8") (pin "6") (pinfunction "6_6") (pintype "passive"))
      (node (ref "CON8") (pin "8") (pinfunction "8_8") (pintype "passive"))
      (node (ref "DISP1") (pin "1") (pinfunction "GND_1") (pintype "passive"))
      (node (ref "FB47") (pin "2") (pinfunction "2_2") (pintype "passive"))
      (node (ref "IC1") (pin "15") (pinfunction "Vss_15") (pintype "power_in"))
      (node (ref "IC1") (pin "31") (pinfunction "AVSS_31") (pintype "power_in"))
      (node (ref "IC1") (pin "36") (pinfunction "Vss_36") (pintype "power_in"))
      (node (ref "IC1") (pin "40") (pinfunction "Vss_40") (pintype "power_in"))
      (node (ref "IC1") (pin "60") (pinfunction "Vss_60") (pintype "power_in"))
      (node (ref "IC1") (pin "65") (pinfunction "Vss_65") (pintype "power_in"))
      (node (ref "IC1") (pin "72") (pinfunction "VssRX_72") (pintype "power_in"))
      (node (ref "IC1") (pin "79") (pinfunction "VssTX_79") (pintype "power_in"))
      (node (ref "IC1") (pin "82") (pinfunction "VssPLL_82") (pintype "power_in"))
      (node (ref "IC1") (pin "85") (pinfunction "Vss_85") (pintype "power_in"))
      (node (ref "IC19") (pin "4") (pinfunction "GND_4") (pintype "passive"))
      (node (ref "IC20") (pin "4") (pinfunction "GND_4") (pintype "passive"))
      (node (ref "IC21") (pin "4") (pinfunction "GND_4") (pintype "power_in"))
      (node (ref "IC37") (pin "2") (pinfunction "2_2") (pintype "passive"))
      (node (ref "IC39") (pin "2") (pinfunction "2_2") (pintype "passive"))
      (node (ref "IC39") (pin "5") (pinfunction "5_5") (pintype "passive"))
      (node (ref "IC40") (pin "14") (pinfunction "X_14") (pintype "passive"))
      (node (ref "IC40") (pin "6") (pinfunction "INH_6") (pintype "input"))
      (node (ref "IC40") (pin "7") (pinfunction "VEE_7") (pintype "passive"))
      (node (ref "IC40") (pin "8") (pinfunction "GND_8") (pintype "power_in"))
      (node (ref "IC41") (pin "2") (pinfunction "2_2") (pintype "passive"))
      (node (ref "IC41") (pin "5") (pinfunction "5_5") (pintype "passive"))
      (node (ref "J6") (pin "9a") (pinfunction "9_9a") (pintype "passive"))
      (node (ref "J6") (pin "9b") (pinfunction "9_9b") (pintype "passive"))
      (node (ref "JP2") (pin "8") (pinfunction "8_8") (pintype "passive"))
      (node (ref "LED1") (pin "K") (pinfunction "K_K") (pintype "passive"))
      (node (ref "LED2") (pin "K") (pinfunction "K_K") (pintype "passive"))
      (node (ref "Q2") (pin "2") (pinfunction "S_2") (pintype "passive"))
      (node (ref "R134") (pin "1") (pinfunction "1_1") (pintype "passive"))
      (node (ref "R154") (pin "1") (pinfunction "1_1") (pintype "passive"))
      (node (ref "R174") (pin "1") (pinfunction "1_1") (pintype "passive"))
      (node (ref "R39") (pin "2") (pinfunction "2_2") (pintype "passive"))
      (node (ref "R9") (pin "1") (pinfunction "1_1") (pintype "passive"))
      (node (ref "RT1") (pin "3") (pintype "passive"))
      (node (ref "S1") (pin "1") (pinfunction "1_1") (pintype "passive"))
      (node (ref "TP5") (pin "1") (pintype "passive"))
    )
    (net (code "74") (name "Net-(C43-Pad1)") (class "Default")
      (node (ref "C43") (pin "1") (pinfunction "1_1") (pintype "passive"))
      (node (ref "R41") (pin "2") (pinfunction "2_2") (pintype "passive"))
    )
    (net (code "75") (name "Net-(C44-Pad1)") (class "Default")
      (node (ref "C44") (pin "1") (pinfunction "1_1") (pintype "passive"))
      (node (ref "R94") (pin "2") (pinfunction "2_2") (pintype "passive"))
    )
    (net (code "76") (name "Net-(C65-Pad1)") (class "Default")
      (node (ref "C65") (pin "1") (pinfunction "1_1") (pintype "passive"))
      (node (ref "R41") (pin "1") (pinfunction "1_1") (pintype "passive"))
      (node (ref "R94") (pin "1") (pinfunction "1_1") (pintype "passive"))
    )
    (net (code "77") (name "Net-(C73-Pad2)") (class "Default")
      (node (ref "C73") (pin "2") (pinfunction "2_2") (pintype "passive"))
      (node (ref "R89") (pin "1") (pinfunction "1_1") (pintype "passive"))
      (node (ref "R90") (pin "1") (pinfunction "1_1") (pintype "passive"))
    )
    (net (code "78") (name "Net-(C74-Pad2)") (class "Default")
      (node (ref "C74") (pin "2") (pinfunction "2_2") (pintype "passive"))
      (node (ref "R91") (pin "1") (pinfunction "1_1") (pintype "passive"))
      (node (ref "R92") (pin "1") (pinfunction "1_1") (pintype "passive"))
    )
    (net (code "79") (name "Net-(C92-Pad2)") (class "Default")
      (node (ref "C92") (pin "2") (pinfunction "2_2") (pintype "passive"))
      (node (ref "CON7") (pin "1") (pinfunction "1_1") (pintype "bidirectional"))
      (node (ref "F6") (pin "1") (pinfunction "1_1") (pintype "passive"))
      (node (ref "R135") (pin "1") (pinfunction "1_1") (pintype "passive"))
      (node (ref "R136") (pin "1") (pinfunction "1_1") (pintype "passive"))
    )
    (net (code "80") (name "Net-(CON1-Pad1)") (class "Default")
      (node (ref "CON1") (pin "1") (pinfunction "1_1") (pintype "passive"))
      (node (ref "R3") (pin "1") (pinfunction "1_1") (pintype "passive"))
      (node (ref "R4") (pin "2") (pinfunction "2_2") (pintype "passive"))
      (node (ref "TP1") (pin "1") (pintype "passive"))
    )
    (net (code "81") (name "Net-(CON1-Pad4)") (class "Default")
      (node (ref "CON1") (pin "4") (pinfunction "4_4") (pintype "passive"))
      (node (ref "R11") (pin "2") (pinfunction "2_2") (pintype "passive"))
      (node (ref "TP4") (pin "1") (pintype "passive"))
    )
    (net (code "82") (name "Net-(CON1-Pad5)") (class "Default")
      (node (ref "CON1") (pin "5") (pinfunction "5_5") (pintype "passive"))
      (node (ref "R12") (pin "2") (pinfunction "2_2") (pintype "passive"))
      (node (ref "TP3") (pin "1") (pintype "passive"))
    )
    (net (code "83") (name "Net-(CON9-Pad1)") (class "Default")
      (node (ref "CON9") (pin "1") (pinfunction "1_1") (pintype "bidirectional"))
      (node (ref "FB47") (pin "1") (pinfunction "1_1") (pintype "passive"))
      (node (ref "IC41") (pin "3") (pinfunction "3_3") (pintype "passive"))
    )
    (net (code "84") (name "Net-(CON9-Pad2)") (class "Default")
      (node (ref "CON9") (pin "2") (pinfunction "2_2") (pintype "bidirectional"))
      (node (ref "FB46") (pin "1") (pinfunction "1_1") (pintype "passive"))
      (node (ref "IC41") (pin "4") (pinfunction "4_4") (pintype "passive"))
    )
    (net (code "85") (name "Net-(DISP1-CONTR)") (class "Default")
      (node (ref "DISP1") (pin "3") (pinfunction "CONTR_3") (pintype "passive"))
      (node (ref "RT1") (pin "2") (pintype "passive"))
    )
    (net (code "86") (name "Net-(DISP1-K)") (class "Default")
      (node (ref "DISP1") (pin "16") (pinfunction "K_16") (pintype "passive"))
      (node (ref "R132") (pin "2") (pinfunction "2_2") (pintype "passive"))
      (node (ref "R133") (pin "2") (pinfunction "2_2") (pintype "passive"))
    )
    (net (code "87") (name "Net-(F6-Pad2)") (class "Default")
      (node (ref "F6") (pin "2") (pinfunction "2_2") (pintype "passive"))
      (node (ref "R26") (pin "1") (pinfunction "1_1") (pintype "passive"))
      (node (ref "R28") (pin "1") (pinfunction "1_1") (pintype "passive"))
    )
    (net (code "88") (name "Net-(F8-Pad1)") (class "Default")
      (node (ref "F8") (pin "1") (pinfunction "1_1") (pintype "passive"))
      (node (ref "FB46") (pin "2") (pinfunction "2_2") (pintype "passive"))
    )
    (net (code "89") (name "Net-(IC1-AVDD)") (class "Default")
      (node (ref "C29") (pin "2") (pinfunction "2_2") (pintype "passive"))
      (node (ref "FB1") (pin "1") (pinfunction "1_1") (pintype "passive"))
      (node (ref "IC1") (pin "30") (pinfunction "AVDD_30") (pintype "power_in"))
    )
    (net (code "90") (name "Net-(IC1-OSC1{slash}CLKI)") (class "Default")
      (node (ref "C39") (pin "2") (pinfunction "2_2") (pintype "passive"))
      (node (ref "IC1") (pin "63") (pinfunction "OSC1/CLKI_63") (pintype "input"))
      (node (ref "R24") (pin "1") (pinfunction "1_1") (pintype "passive"))
      (node (ref "X1") (pin "1") (pinfunction "1_1") (pintype "passive"))
    )
    (net (code "91") (name "Net-(IC1-OSC2{slash}CLKO)") (class "Default")
      (node (ref "C40") (pin "2") (pinfunction "2_2") (pintype "passive"))
      (node (ref "IC1") (pin "64") (pinfunction "OSC2/CLKO_64") (pintype "output"))
      (node (ref "R24") (pin "2") (pinfunction "2_2") (pintype "passive"))
      (node (ref "X1") (pin "2") (pinfunction "2_2") (pintype "passive"))
    )
    (net (code "92") (name "Net-(IC1-RBIAS)") (class "Default")
      (node (ref "IC1") (pin "80") (pinfunction "RBIAS_80") (pintype "passive"))
      (node (ref "R39") (pin "1") (pinfunction "1_1") (pintype "passive"))
    )
    (net (code "93") (name "Net-(IC1-RF0{slash}AN5)") (class "Default")
      (node (ref "C114") (pin "2") (pinfunction "2_2") (pintype "passive"))
      (node (ref "IC1") (pin "12") (pinfunction "RF0/AN5_12") (pintype "bidirectional"))
      (node (ref "R173") (pin "2") (pinfunction "2_2") (pintype "passive"))
    )
    (net (code "94") (name "Net-(IC1-VDDCORE{slash}VCAP)") (class "Default")
      (node (ref "C32") (pin "2") (pinfunction "2_2") (pintype "passive"))
      (node (ref "C4") (pin "2") (pinfunction "2_2") (pintype "passive"))
      (node (ref "IC1") (pin "16") (pinfunction "VDDCORE/VCAP_16") (pintype "power_in"))
    )
    (net (code "95") (name "Net-(IC21-Vbat)") (class "Default")
      (node (ref "BH1") (pin "pos1") (pinfunction "+_pos1") (pintype "power_in"))
      (node (ref "BH1") (pin "pos2") (pinfunction "+_pos2") (pintype "power_in"))
      (node (ref "C34") (pin "1") (pinfunction "1_1") (pintype "passive"))
      (node (ref "IC21") (pin "3") (pinfunction "Vbat_3") (pintype "power_in"))
    )
    (net (code "96") (name "Net-(IC21-X1)") (class "Default")
      (node (ref "IC21") (pin "1") (pinfunction "X1_1") (pintype "passive"))
      (node (ref "X2") (pin "1") (pinfunction "1_1") (pintype "passive"))
    )
    (net (code "97") (name "Net-(IC21-X2)") (class "Default")
      (node (ref "C18") (pin "1") (pinfunction "1_1") (pintype "passive"))
      (node (ref "IC21") (pin "2") (pinfunction "X2_2") (pintype "passive"))
      (node (ref "X2") (pin "4") (pinfunction "4_4") (pintype "passive"))
    )
    (net (code "98") (name "Net-(IC37-Pad5)") (class "Default")
      (node (ref "IC37") (pin "5") (pinfunction "5_5") (pintype "passive"))
      (node (ref "R43") (pin "2") (pinfunction "2_2") (pintype "passive"))
    )
    (net (code "99") (name "Net-(LED1-PadA)") (class "Default")
      (node (ref "LED1") (pin "A") (pinfunction "A_A") (pintype "passive"))
      (node (ref "R10") (pin "1") (pinfunction "1_1") (pintype "passive"))
    )
    (net (code "100") (name "Net-(LED2-PadA)") (class "Default")
      (node (ref "LED2") (pin "A") (pinfunction "A_A") (pintype "passive"))
      (node (ref "R21") (pin "1") (pinfunction "1_1") (pintype "passive"))
    )
    (net (code "101") (name "Net-(Q2-D)") (class "Default")
      (node (ref "Q2") (pin "3") (pinfunction "D_3") (pintype "passive"))
      (node (ref "R132") (pin "1") (pinfunction "1_1") (pintype "passive"))
      (node (ref "R133") (pin "1") (pinfunction "1_1") (pintype "passive"))
    )
    (net (code "102") (name "Net-(R156-Pad2)") (class "Default")
      (node (ref "R156") (pin "2") (pinfunction "2_2") (pintype "passive"))
      (node (ref "R8") (pin "1") (pinfunction "1_1") (pintype "passive"))
    )
    (net (code "103") (name "Net-(Tr3-RDCT)") (class "Default")
      (node (ref "C76") (pin "2") (pinfunction "2_2") (pintype "passive"))
      (node (ref "Tr3") (pin "7") (pinfunction "RDCT_7") (pintype "passive"))
    )
    (net (code "104") (name "Net-(Tr3-RX+)") (class "Default")
      (node (ref "J6") (pin "3") (pinfunction "3_3") (pintype "passive"))
      (node (ref "Tr3") (pin "11") (pinfunction "RX+_11") (pintype "power_in"))
    )
    (net (code "105") (name "Net-(Tr3-RX-)") (class "Default")
      (node (ref "J6") (pin "6") (pinfunction "6_6") (pintype "passive"))
      (node (ref "Tr3") (pin "9") (pinfunction "RX-_9") (pintype "power_in"))
    )
    (net (code "106") (name "Net-(Tr3-RXCT)") (class "Default")
      (node (ref "C43") (pin "2") (pinfunction "2_2") (pintype "passive"))
      (node (ref "Tr3") (pin "10") (pinfunction "RXCT_10") (pintype "power_in"))
    )
    (net (code "107") (name "Net-(Tr3-TDCT)") (class "Default")
      (node (ref "C75") (pin "2") (pinfunction "2_2") (pintype "passive"))
      (node (ref "FB2") (pin "2") (pinfunction "2_2") (pintype "passive"))
      (node (ref "Tr3") (pin "2") (pinfunction "TDCT_2") (pintype "passive"))
    )
    (net (code "108") (name "Net-(Tr3-TX+)") (class "Default")
      (node (ref "J6") (pin "1") (pinfunction "1_1") (pintype "passive"))
      (node (ref "Tr3") (pin "16") (pinfunction "TX+_16") (pintype "power_in"))
    )
    (net (code "109") (name "Net-(Tr3-TX-)") (class "Default")
      (node (ref "J6") (pin "2") (pinfunction "2_2") (pintype "passive"))
      (node (ref "Tr3") (pin "14") (pinfunction "TX-_14") (pintype "power_in"))
    )
    (net (code "110") (name "Net-(Tr3-TXCT)") (class "Default")
      (node (ref "C44") (pin "2") (pinfunction "2_2") (pintype "passive"))
      (node (ref "Tr3") (pin "15") (pinfunction "TXCT_15") (pintype "power_in"))
    )
    (net (code "111") (name "P3V3") (class "Default")
      (node (ref "C10") (pin "1") (pinfunction "1_1") (pintype "passive"))
      (node (ref "C100") (pin "1") (pinfunction "1_1") (pintype "passive"))
      (node (ref "C102") (pin "1") (pinfunction "1_1") (pintype "passive"))
      (node (ref "C103") (pin "1") (pinfunction "1_1") (pintype "passive"))
      (node (ref "C104") (pin "1") (pinfunction "1_1") (pintype "passive"))
      (node (ref "C107") (pin "1") (pinfunction "1_1") (pintype "passive"))
      (node (ref "C11") (pin "1") (pinfunction "1_1") (pintype "passive"))
      (node (ref "C17") (pin "1") (pinfunction "1_1") (pintype "passive"))
      (node (ref "C31") (pin "2") (pinfunction "2_2") (pintype "passive"))
      (node (ref "C35") (pin "1") (pinfunction "1_1") (pintype "passive"))
      (node (ref "C38") (pin "1") (pinfunction "1_1") (pintype "passive"))
      (node (ref "C8") (pin "2") (pinfunction "2_2") (pintype "passive"))
      (node (ref "C9") (pin "1") (pinfunction "1_1") (pintype "passive"))
      (node (ref "C95") (pin "1") (pinfunction "1_1") (pintype "passive"))
      (node (ref "C99") (pin "1") (pinfunction "1_1") (pintype "passive"))
      (node (ref "CON1") (pin "2") (pinfunction "2_2") (pintype "passive"))
      (node (ref "CON8") (pin "2") (pinfunction "2_2") (pintype "passive"))
      (node (ref "CON8") (pin "4") (pinfunction "4_4") (pintype "passive"))
      (node (ref "FB1") (pin "2") (pinfunction "2_2") (pintype "passive"))
      (node (ref "FB2") (pin "1") (pinfunction "1_1") (pintype "passive"))
      (node (ref "IC1") (pin "17") (pinfunction "Vdd_17") (pintype "power_in"))
      (node (ref "IC1") (pin "29") (pinfunction "ENVREG_29") (pintype "input"))
      (node (ref "IC1") (pin "37") (pinfunction "Vdd_37") (pintype "power_in"))
      (node (ref "IC1") (pin "59") (pinfunction "Vdd_59") (pintype "power_in"))
      (node (ref "IC1") (pin "62") (pinfunction "Vdd_62") (pintype "power_in"))
      (node (ref "IC1") (pin "75") (pinfunction "VddRX_75") (pintype "power_in"))
      (node (ref "IC1") (pin "76") (pinfunction "VddTX_76") (pintype "power_in"))
      (node (ref "IC1") (pin "81") (pinfunction "VddPLL_81") (pintype "power_in"))
      (node (ref "IC1") (pin "86") (pinfunction "Vdd_86") (pintype "power_in"))
      (node (ref "IC19") (pin "3") (pinfunction "WP#_3") (pintype "input"))
      (node (ref "IC19") (pin "7") (pinfunction "HOLD#_7") (pintype "input"))
      (node (ref "IC19") (pin "8") (pinfunction "Vcc_8") (pintype "passive"))
      (node (ref "IC20") (pin "3") (pinfunction "WP#_3") (pintype "input"))
      (node (ref "IC20") (pin "7") (pinfunction "HOLD#_7") (pintype "input"))
      (node (ref "IC20") (pin "8") (pinfunction "Vcc_8") (pintype "passive"))
      (node (ref "IC21") (pin "8") (pinfunction "VCC_8") (pintype "power_in"))
      (node (ref "IC40") (pin "16") (pinfunction "VCC_16") (pintype "power_in"))
      (node (ref "JP2") (pin "10") (pinfunction "10_10") (pintype "passive"))
      (node (ref "R1") (pin "2") (pinfunction "2_2") (pintype "passive"))
      (node (ref "R2") (pin "2") (pinfunction "2_2") (pintype "passive"))
      (node (ref "R28") (pin "2") (pinfunction "2_2") (pintype "passive"))
      (node (ref "R29") (pin "1") (pinfunction "1_1") (pintype "passive"))
      (node (ref "R3") (pin "2") (pinfunction "2_2") (pintype "passive"))
      (node (ref "R43") (pin "1") (pinfunction "1_1") (pintype "passive"))
      (node (ref "R5") (pin "1") (pinfunction "1_1") (pintype "passive"))
      (node (ref "TP2") (pin "1") (pintype "passive"))
    )
    (net (code "112") (name "P5V0") (class "Default")
      (node (ref "C94") (pin "2") (pinfunction "2_2") (pintype "passive"))
      (node (ref "CON5") (pin "10") (pinfunction "10_10") (pintype "passive"))
      (node (ref "CON8") (pin "10") (pinfunction "10_10") (pintype "passive"))
      (node (ref "DISP1") (pin "15") (pinfunction "A_15") (pintype "passive"))
      (node (ref "DISP1") (pin "2") (pinfunction "VCC_2") (pintype "passive"))
      (node (ref "R26") (pin "2") (pinfunction "2_2") (pintype "passive"))
      (node (ref "RT1") (pin "1") (pintype "passive"))
    )
    (net (code "113") (name "P12V0") (class "Default")
      (node (ref "R8") (pin "2") (pinfunction "2_2") (pintype "passive"))
    )
    (net (code "114") (name "unconnected-(CON1-Pad6)") (class "Default")
      (node (ref "CON1") (pin "6") (pinfunction "6_6") (pintype "passive"))
    )
    (net (code "115") (name "unconnected-(CON8-Pad12)") (class "Default")
      (node (ref "CON8") (pin "12") (pinfunction "12_12") (pintype "passive"))
    )
    (net (code "116") (name "unconnected-(CON8-Pad14)") (class "Default")
      (node (ref "CON8") (pin "14") (pinfunction "14_14") (pintype "passive"))
    )
    (net (code "117") (name "unconnected-(CON8-Pad16)") (class "Default")
      (node (ref "CON8") (pin "16") (pinfunction "16_16") (pintype "passive"))
    )
    (net (code "118") (name "unconnected-(CON8-Pad20)") (class "Default")
      (node (ref "CON8") (pin "20") (pinfunction "20_20") (pintype "passive"))
    )
    (net (code "119") (name "unconnected-(DISP1-D0-Pad7)") (class "Default")
      (node (ref "DISP1") (pin "7") (pinfunction "D0_7") (pintype "passive"))
    )
    (net (code "120") (name "unconnected-(DISP1-D1-Pad8)") (class "Default")
      (node (ref "DISP1") (pin "8") (pinfunction "D1_8") (pintype "passive"))
    )
    (net (code "121") (name "unconnected-(DISP1-D2-Pad9)") (class "Default")
      (node (ref "DISP1") (pin "9") (pinfunction "D2_9") (pintype "passive"))
    )
    (net (code "122") (name "unconnected-(DISP1-D3-Pad10)") (class "Default")
      (node (ref "DISP1") (pin "10") (pinfunction "D3_10") (pintype "passive"))
    )
    (net (code "123") (name "unconnected-(IC1-RB5{slash}KBI1-Pad68)") (class "Default")
      (node (ref "IC1") (pin "68") (pinfunction "RB5/KBI1_68") (pintype "bidirectional"))
    )
    (net (code "124") (name "unconnected-(IC1-RE0{slash}AD8{slash}~{RD}{slash}P2D-Pad4)") (class "Default")
      (node (ref "IC1") (pin "4") (pinfunction "RE0/AD8/~{RD}/P2D_4") (pintype "bidirectional"))
    )
    (net (code "125") (name "unconnected-(IC1-RE1{slash}AD9{slash}~{WR}{slash}P2C-Pad3)") (class "Default")
      (node (ref "IC1") (pin "3") (pinfunction "RE1/AD9/~{WR}/P2C_3") (pintype "bidirectional"))
    )
    (net (code "126") (name "unconnected-(IC1-RE2{slash}AD10{slash}~{CS}{slash}P2B-Pad98)") (class "Default")
      (node (ref "IC1") (pin "98") (pinfunction "RE2/AD10/~{CS}/P2B_98") (pintype "bidirectional"))
    )
    (net (code "127") (name "unconnected-(IC1-RE3{slash}AD11{slash}P3C-Pad97)") (class "Default")
      (node (ref "IC1") (pin "97") (pinfunction "RE3/AD11/P3C_97") (pintype "bidirectional"))
    )
    (net (code "128") (name "unconnected-(IC1-RG3{slash}CCP4{slash}P3D-Pad51)") (class "Default")
      (node (ref "IC1") (pin "51") (pinfunction "RG3/CCP4/P3D_51") (pintype "bidirectional"))
    )
    (net (code "129") (name "unconnected-(IC1-RG4{slash}CCP5{slash}P1D-Pad14)") (class "Default")
      (node (ref "IC1") (pin "14") (pinfunction "RG4/CCP5/P1D_14") (pintype "bidirectional"))
    )
    (net (code "130") (name "unconnected-(IC1-RG7-Pad38)") (class "Default")
      (node (ref "IC1") (pin "38") (pinfunction "RG7_38") (pintype "bidirectional"))
    )
    (net (code "131") (name "unconnected-(IC1-RH0{slash}A16-Pad99)") (class "Default")
      (node (ref "IC1") (pin "99") (pinfunction "RH0/A16_99") (pintype "bidirectional"))
    )
    (net (code "132") (name "unconnected-(IC1-RH1{slash}A17-Pad100)") (class "Default")
      (node (ref "IC1") (pin "100") (pinfunction "RH1/A17_100") (pintype "bidirectional"))
    )
    (net (code "133") (name "unconnected-(IC1-RH3{slash}A19-Pad2)") (class "Default")
      (node (ref "IC1") (pin "2") (pinfunction "RH3/A19_2") (pintype "bidirectional"))
    )
    (net (code "134") (name "unconnected-(IC1-RJ2{slash}~{WRL}-Pad66)") (class "Default")
      (node (ref "IC1") (pin "66") (pinfunction "RJ2/~{WRL}_66") (pintype "bidirectional"))
    )
    (net (code "135") (name "unconnected-(IC1-RJ6{slash}~{LB}-Pad58)") (class "Default")
      (node (ref "IC1") (pin "58") (pinfunction "RJ6/~{LB}_58") (pintype "bidirectional"))
    )
    (net (code "136") (name "unconnected-(IC1-nc-Pad9)") (class "Default")
      (node (ref "IC1") (pin "9") (pinfunction "nc_9") (pintype "passive"))
    )
    (net (code "137") (name "unconnected-(IC39-Pad1)") (class "Default")
      (node (ref "IC39") (pin "1") (pinfunction "1_1") (pintype "passive"))
    )
    (net (code "138") (name "unconnected-(IC39-Pad6)") (class "Default")
      (node (ref "IC39") (pin "6") (pinfunction "6_6") (pintype "passive"))
    )
    (net (code "139") (name "unconnected-(IC40-X0-Pad12)") (class "Default")
      (node (ref "IC40") (pin "12") (pinfunction "X0_12") (pintype "passive"))
    )
    (net (code "140") (name "unconnected-(IC40-X1-Pad13)") (class "Default")
      (node (ref "IC40") (pin "13") (pinfunction "X1_13") (pintype "passive"))
    )
    (net (code "141") (name "unconnected-(IC41-Pad1)") (class "Default")
      (node (ref "IC41") (pin "1") (pinfunction "1_1") (pintype "passive"))
    )
    (net (code "142") (name "unconnected-(IC41-Pad6)") (class "Default")
      (node (ref "IC41") (pin "6") (pinfunction "6_6") (pintype "passive"))
    )
    (net (code "143") (name "unconnected-(JP2-Pad6)") (class "Default")
      (node (ref "JP2") (pin "6") (pinfunction "6_6") (pintype "passive"))
    )
  )
)
